# I2C_header.net
KiCad netlist of a schematic drawn in EAGLE
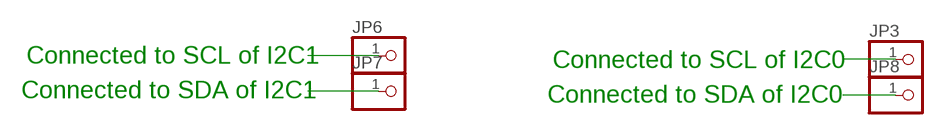
[diagram p0: schematic, sheet 1]

(export (version "E")
  (design (tool "Eeschema 10.0.6"))
  (components
    (comp (ref "JP3")
      (value "PINHD-1X1")
      (footprint "eagle-import:1X01")
      (libsource (lib "eagle-import") (part "PINHD-1X1"))
    )
    (comp (ref "JP6")
      (value "PINHD-1X1")
      (footprint "eagle-import:1X01")
      (libsource (lib "eagle-import") (part "PINHD-1X1"))
    )
    (comp (ref "JP7")
      (value "PINHD-1X1")
      (footprint "eagle-import:1X01")
      (libsource (lib "eagle-import") (part "PINHD-1X1"))
    )
    (comp (ref "JP8")
      (value "PINHD-1X1")
      (footprint "eagle-import:1X01")
      (libsource (lib "eagle-import") (part "PINHD-1X1"))
    )
  )
  (nets
    (net (code "1") (name "/SCL") (class "Default")
      (node (ref "JP3") (pin "1") (pinfunction "1_1") (pintype "passive"))
      (node (ref "JP6") (pin "1") (pinfunction "1_1") (pintype "passive"))
    )
    (net (code "2") (name "/SDA") (class "Default")
      (node (ref "JP7") (pin "1") (pinfunction "1_1") (pintype "passive"))
      (node (ref "JP8") (pin "1") (pinfunction "1_1") (pintype "passive"))
    )
  )
)
